# power.net
KiCad netlist of a schematic drawn in EAGLE
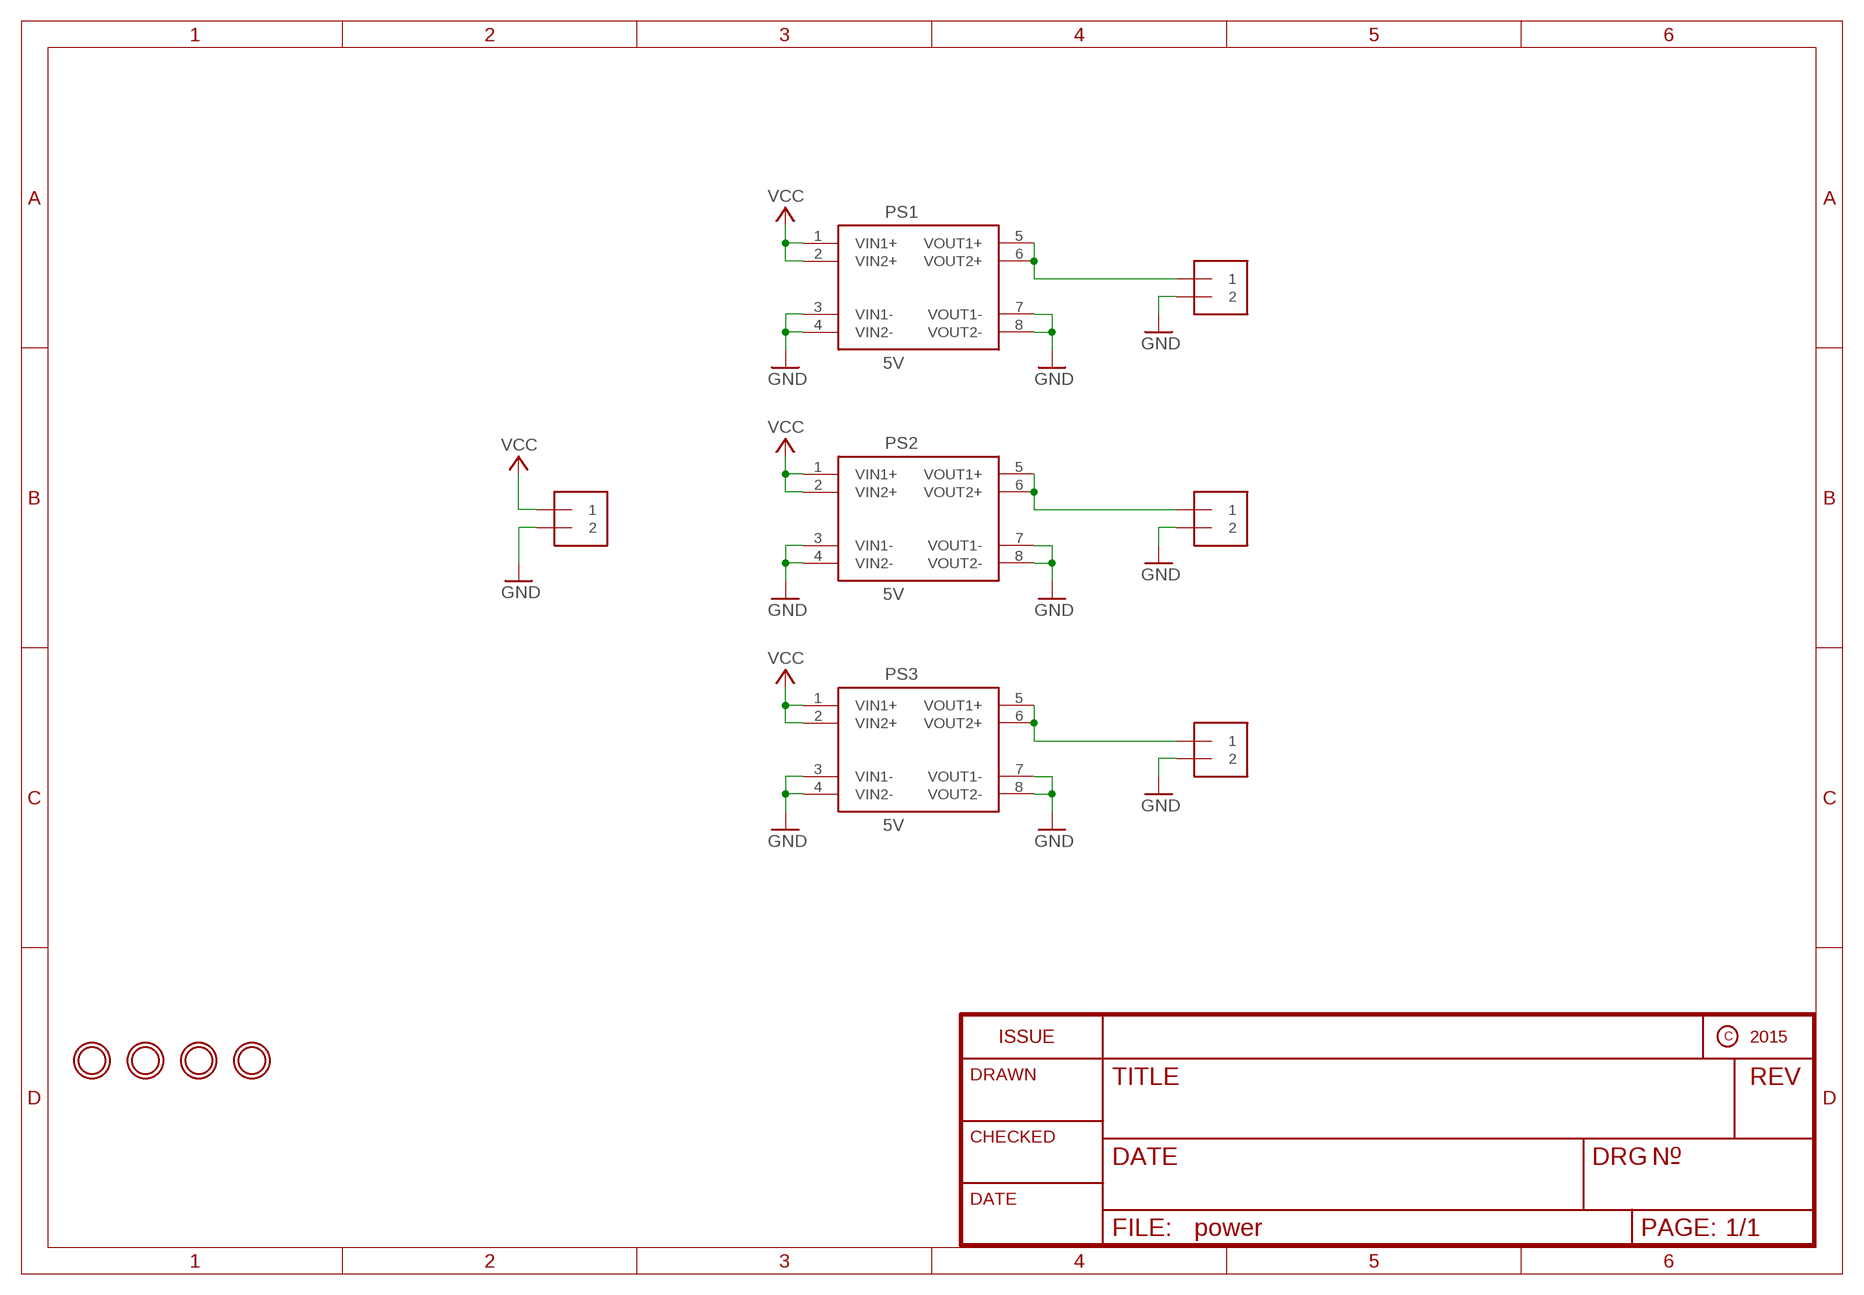
[diagram p0: schematic, sheet 1]

(export (version "E")
  (design (tool "Eeschema 10.0.6"))
  (components
    (comp (ref "J1")
      (value "1X2-3.5MM")
      (footprint "eagle-import:1X2-3.5MM")
      (libsource (lib "eagle-import") (part "1X2-3.5MM"))
    )
    (comp (ref "J2")
      (value "1X2-3.5MM")
      (footprint "eagle-import:1X2-3.5MM")
      (libsource (lib "eagle-import") (part "1X2-3.5MM"))
    )
    (comp (ref "J3")
      (value "1X2-3.5MM")
      (footprint "eagle-import:1X2-3.5MM")
      (libsource (lib "eagle-import") (part "1X2-3.5MM"))
    )
    (comp (ref "J4")
      (value "1X2-3.5MM")
      (footprint "eagle-import:1X2-3.5MM")
      (libsource (lib "eagle-import") (part "1X2-3.5MM"))
    )
    (comp (ref "PS1")
      (value "5V")
      (footprint "eagle-import:K8801")
      (libsource (lib "eagle-import") (part "K8801MODULE"))
    )
    (comp (ref "PS2")
      (value "5V")
      (footprint "eagle-import:K8801")
      (libsource (lib "eagle-import") (part "K8801MODULE"))
    )
    (comp (ref "PS3")
      (value "5V")
      (footprint "eagle-import:K8801")
      (libsource (lib "eagle-import") (part "K8801MODULE"))
    )
    (comp (ref "U$1")
      (value "MICROBUILDER_MOUNTINGHOLE2.5")
      (footprint "eagle-import:MICROBUILDER_MOUNTINGHOLE_2.5_PLATED")
      (libsource (lib "eagle-import") (part "MICROBUILDER_MOUNTINGHOLE2.5"))
    )
    (comp (ref "U$2")
      (value "MICROBUILDER_MOUNTINGHOLE2.5")
      (footprint "eagle-import:MICROBUILDER_MOUNTINGHOLE_2.5_PLATED")
      (libsource (lib "eagle-import") (part "MICROBUILDER_MOUNTINGHOLE2.5"))
    )
    (comp (ref "U$3")
      (value "MICROBUILDER_MOUNTINGHOLE2.5")
      (footprint "eagle-import:MICROBUILDER_MOUNTINGHOLE_2.5_PLATED")
      (libsource (lib "eagle-import") (part "MICROBUILDER_MOUNTINGHOLE2.5"))
    )
    (comp (ref "U$4")
      (value "MICROBUILDER_MOUNTINGHOLE2.5")
      (footprint "eagle-import:MICROBUILDER_MOUNTINGHOLE_2.5_PLATED")
      (libsource (lib "eagle-import") (part "MICROBUILDER_MOUNTINGHOLE2.5"))
    )
  )
  (nets
    (net (code "1") (name "GND") (class "Default")
      (node (ref "J1") (pin "2") (pinfunction "2_2") (pintype "passive"))
      (node (ref "J2") (pin "2") (pinfunction "2_2") (pintype "passive"))
      (node (ref "J3") (pin "2") (pinfunction "2_2") (pintype "passive"))
      (node (ref "J4") (pin "2") (pinfunction "2_2") (pintype "passive"))
      (node (ref "PS1") (pin "3") (pinfunction "VIN1-_3") (pintype "bidirectional"))
      (node (ref "PS1") (pin "4") (pinfunction "VIN2-_4") (pintype "bidirectional"))
      (node (ref "PS1") (pin "7") (pinfunction "VOUT1-_7") (pintype "bidirectional"))
      (node (ref "PS1") (pin "8") (pinfunction "VOUT2-_8") (pintype "bidirectional"))
      (node (ref "PS2") (pin "3") (pinfunction "VIN1-_3") (pintype "bidirectional"))
      (node (ref "PS2") (pin "4") (pinfunction "VIN2-_4") (pintype "bidirectional"))
      (node (ref "PS2") (pin "7") (pinfunction "VOUT1-_7") (pintype "bidirectional"))
      (node (ref "PS2") (pin "8") (pinfunction "VOUT2-_8") (pintype "bidirectional"))
      (node (ref "PS3") (pin "3") (pinfunction "VIN1-_3") (pintype "bidirectional"))
      (node (ref "PS3") (pin "4") (pinfunction "VIN2-_4") (pintype "bidirectional"))
      (node (ref "PS3") (pin "7") (pinfunction "VOUT1-_7") (pintype "bidirectional"))
      (node (ref "PS3") (pin "8") (pinfunction "VOUT2-_8") (pintype "bidirectional"))
    )
    (net (code "2") (name "Net-(PS1-VOUT1+)") (class "Default")
      (node (ref "J2") (pin "1") (pinfunction "1_1") (pintype "passive"))
      (node (ref "PS1") (pin "5") (pinfunction "VOUT1+_5") (pintype "bidirectional"))
      (node (ref "PS1") (pin "6") (pinfunction "VOUT2+_6") (pintype "bidirectional"))
    )
    (net (code "3") (name "Net-(PS2-VOUT1+)") (class "Default")
      (node (ref "J3") (pin "1") (pinfunction "1_1") (pintype "passive"))
      (node (ref "PS2") (pin "5") (pinfunction "VOUT1+_5") (pintype "bidirectional"))
      (node (ref "PS2") (pin "6") (pinfunction "VOUT2+_6") (pintype "bidirectional"))
    )
    (net (code "4") (name "Net-(PS3-VOUT1+)") (class "Default")
      (node (ref "J4") (pin "1") (pinfunction "1_1") (pintype "passive"))
      (node (ref "PS3") (pin "5") (pinfunction "VOUT1+_5") (pintype "bidirectional"))
      (node (ref "PS3") (pin "6") (pinfunction "VOUT2+_6") (pintype "bidirectional"))
    )
    (net (code "5") (name "VCC") (class "Default")
      (node (ref "J1") (pin "1") (pinfunction "1_1") (pintype "passive"))
      (node (ref "PS1") (pin "1") (pinfunction "VIN1+_1") (pintype "bidirectional"))
      (node (ref "PS1") (pin "2") (pinfunction "VIN2+_2") (pintype "bidirectional"))
      (node (ref "PS2") (pin "1") (pinfunction "VIN1+_1") (pintype "bidirectional"))
      (node (ref "PS2") (pin "2") (pinfunction "VIN2+_2") (pintype "bidirectional"))
      (node (ref "PS3") (pin "1") (pinfunction "VIN1+_1") (pintype "bidirectional"))
      (node (ref "PS3") (pin "2") (pinfunction "VIN2+_2") (pintype "bidirectional"))
    )
  )
)
